# STM32.net
KiCad netlist of a schematic drawn in Altium Designer
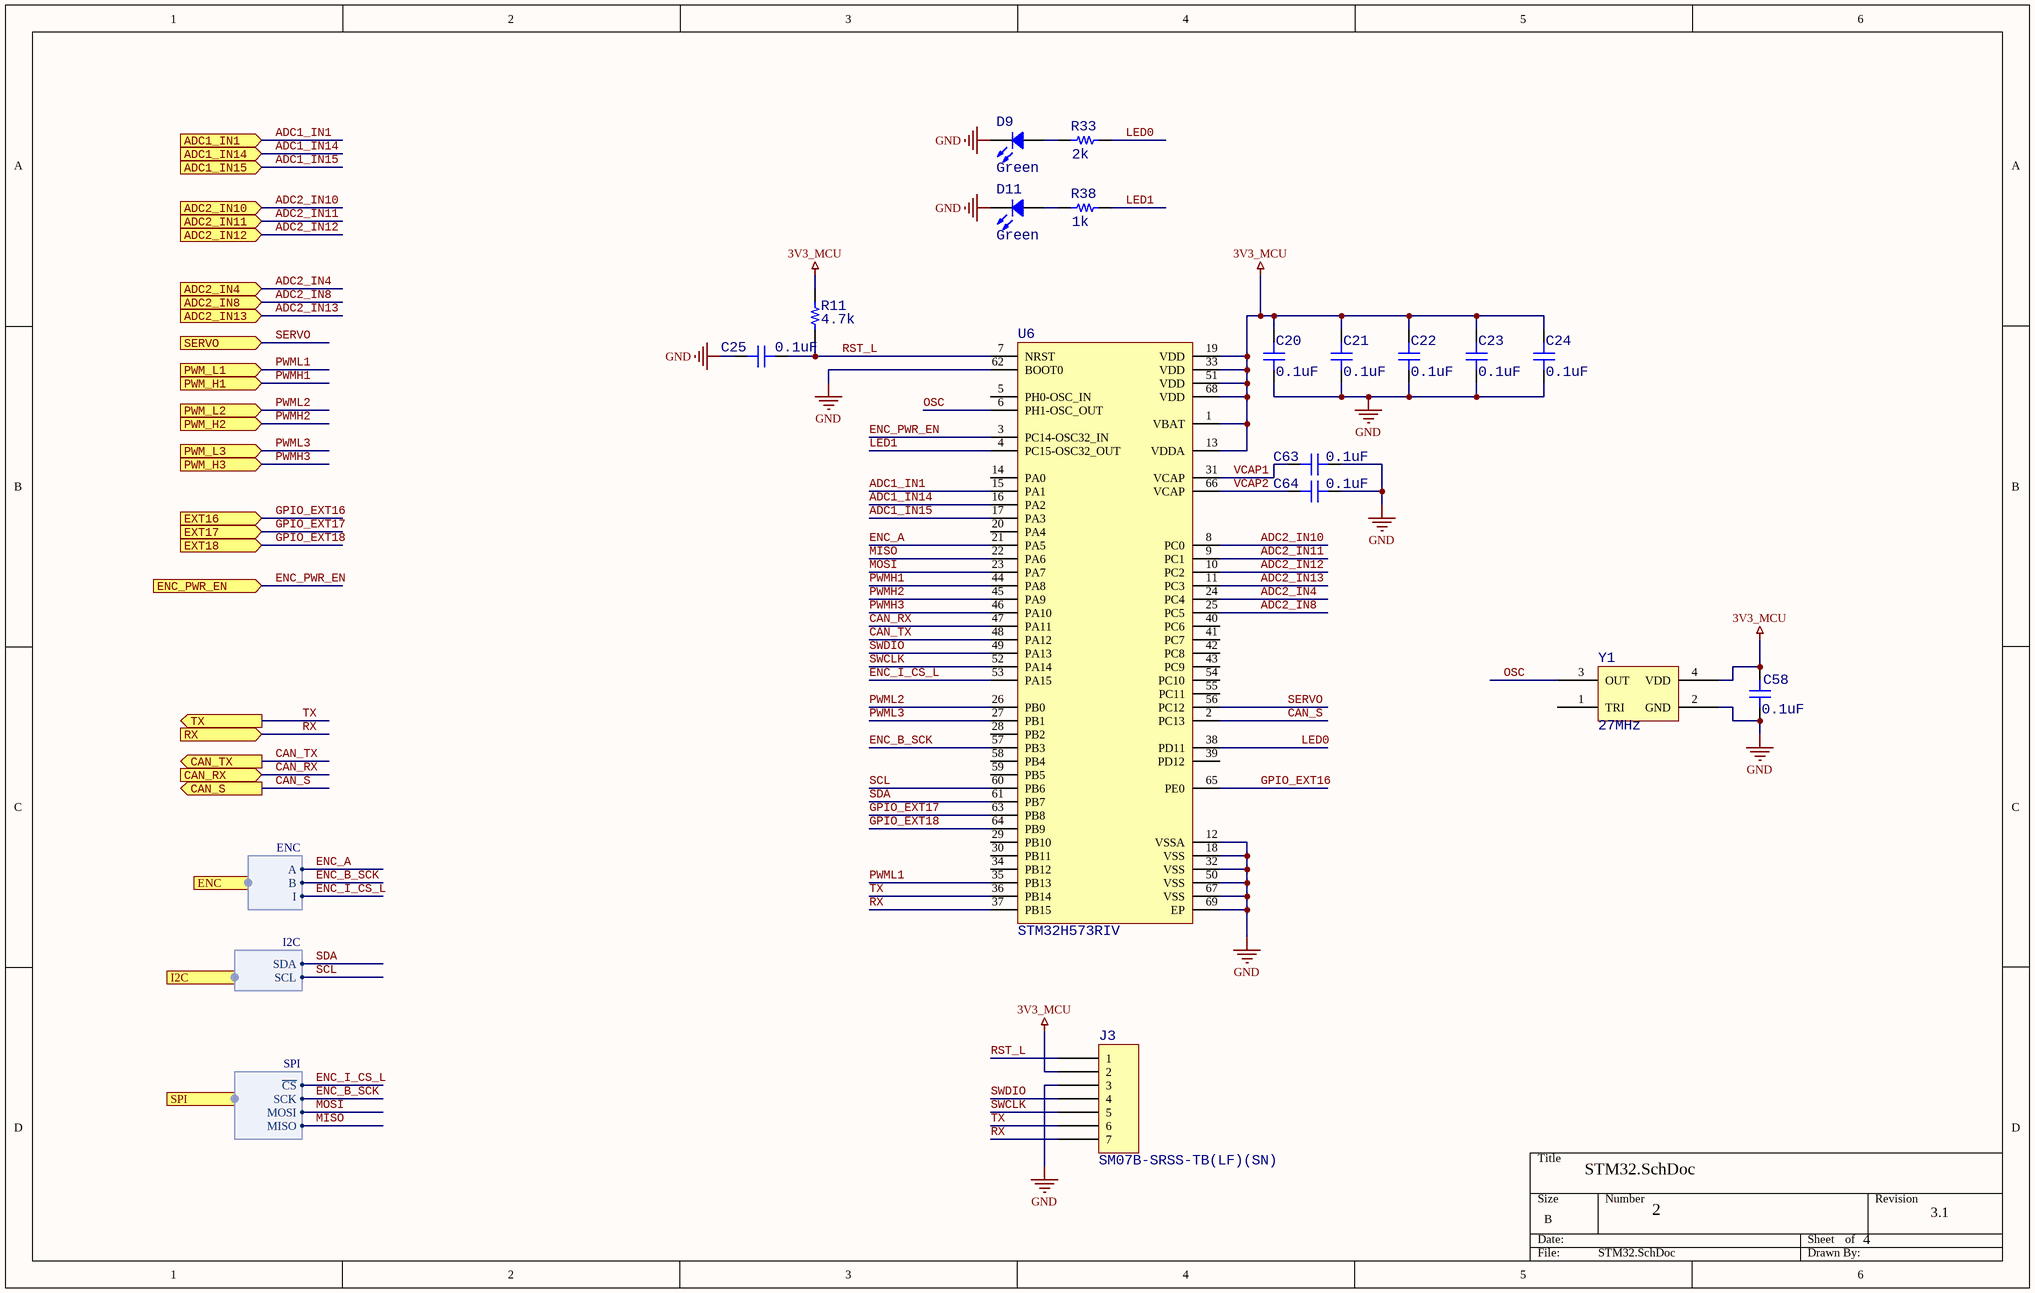
[diagram p0: STM32.SchDoc]

(export (version "E")
  (design (tool "Eeschema 10.0.6"))
  (components
    (comp (ref "C20")
      (value "0.1uF")
      (footprint "CAP_0402")
      (description "CAP CER 402")
      (libsource (lib "IC") (part "CAP_0402"))
    )
    (comp (ref "C21")
      (value "0.1uF")
      (footprint "CAP_0402")
      (description "CAP CER 402")
      (libsource (lib "IC") (part "CAP_0402"))
    )
    (comp (ref "C22")
      (value "0.1uF")
      (footprint "CAP_0402")
      (description "CAP CER 402")
      (libsource (lib "IC") (part "CAP_0402"))
    )
    (comp (ref "C23")
      (value "0.1uF")
      (footprint "CAP_0402")
      (description "CAP CER 402")
      (libsource (lib "IC") (part "CAP_0402"))
    )
    (comp (ref "C24")
      (value "0.1uF")
      (footprint "CAP_0402")
      (description "CAP CER 402")
      (libsource (lib "IC") (part "CAP_0402"))
    )
    (comp (ref "C25")
      (value "0.1uF")
      (footprint "CAP_0402")
      (description "CAP CER 402")
      (libsource (lib "IC") (part "CAP_0402"))
    )
    (comp (ref "C58")
      (value "0.1uF")
      (footprint "CAP_0402")
      (description "CAP CER 402")
      (libsource (lib "IC") (part "CAP_0402"))
    )
    (comp (ref "C63")
      (value "0.1uF")
      (footprint "CAP_0402")
      (description "CAP CER 402")
      (libsource (lib "IC") (part "CAP_0402"))
    )
    (comp (ref "C64")
      (value "0.1uF")
      (footprint "CAP_0402")
      (description "CAP CER 402")
      (libsource (lib "IC") (part "CAP_0402"))
    )
    (comp (ref "D9")
      (value "Green")
      (footprint "LED 0603_1608 GREEN")
      (description "LED GREEN CLEAR 2SMD")
      (fields (field (name "PART NUMBER") "XZCDGK53W-8VF") (field (name "MANUFACTURER") "SunLED"))
      (libsource (lib "Celestial Altium Library - altium_library") (part "LED"))
    )
    (comp (ref "D11")
      (value "Green")
      (footprint "LED 0603_1608 GREEN")
      (description "LED GREEN CLEAR 2SMD")
      (fields (field (name "PART NUMBER") "XZCDGK53W-8VF") (field (name "MANUFACTURER") "SunLED"))
      (libsource (lib "Celestial Altium Library - altium_library") (part "LED"))
    )
    (comp (ref "J3")
      (value "SM07B-SRSS-TB(LF)(SN)")
      (footprint "JST SM07B-SRSS-TB")
      (description "CONN HEADER SMD R/A 7POS 1MM")
      (fields (field (name "MANUFACTURER") "JST Sales America Inc."))
      (libsource (lib "Celestial Altium Library - altium_library") (part "7 Pin"))
    )
    (comp (ref "R11")
      (value "4.7k")
      (footprint "RES_0402")
      (description "RES 0402")
      (libsource (lib "IC") (part "RES_0402"))
    )
    (comp (ref "R33")
      (value "2k")
      (footprint "RES_0402")
      (description "RES 0402")
      (libsource (lib "IC") (part "RES_0402"))
    )
    (comp (ref "R38")
      (value "1k")
      (footprint "RES_0402")
      (description "RES 0402")
      (libsource (lib "IC") (part "RES_0402"))
    )
    (comp (ref "U6")
      (value "STM32H573RIV")
      (footprint "68-VFQFPN")
      (libsource (lib "IC") (part "STM32H573RIV"))
    )
    (comp (ref "Y1")
      (value "27MHz")
      (footprint "ABRACON ASD")
      (description "XTAL OSC XO 27.0000MHZ HCMOS SMD")
      (fields (field (name "PART NUMBER") "ASD3-27.000MHZ-EC-T") (field (name "MANUFACTURER") "Abracon LLC"))
      (libsource (lib "Celestial Altium Library - altium_library") (part "Abracon XO ASD"))
    )
  )
  (nets
    (net (code "4") (name "/ADC1_IN1") (class "Default")
      (node (ref "U6") (pin "15") (pinfunction "PA1_15") (pintype "passive"))
    )
    (net (code "5") (name "/ADC1_IN14") (class "Default")
      (node (ref "U6") (pin "16") (pinfunction "PA2_16") (pintype "passive"))
    )
    (net (code "6") (name "/ADC1_IN15") (class "Default")
      (node (ref "U6") (pin "17") (pinfunction "PA3_17") (pintype "passive"))
    )
    (net (code "7") (name "/ADC2_IN4") (class "Default")
      (node (ref "U6") (pin "24") (pinfunction "PC4_24") (pintype "passive"))
    )
    (net (code "8") (name "/ADC2_IN8") (class "Default")
      (node (ref "U6") (pin "25") (pinfunction "PC5_25") (pintype "passive"))
    )
    (net (code "9") (name "/ADC2_IN10") (class "Default")
      (node (ref "U6") (pin "8") (pinfunction "PC0_8") (pintype "passive"))
    )
    (net (code "10") (name "/ADC2_IN11") (class "Default")
      (node (ref "U6") (pin "9") (pinfunction "PC1_9") (pintype "passive"))
    )
    (net (code "11") (name "/ADC2_IN12") (class "Default")
      (node (ref "U6") (pin "10") (pinfunction "PC2_10") (pintype "passive"))
    )
    (net (code "12") (name "/ADC2_IN13") (class "Default")
      (node (ref "U6") (pin "11") (pinfunction "PC3_11") (pintype "passive"))
    )
    (net (code "13") (name "/CAN_RX") (class "Default")
      (node (ref "U6") (pin "47") (pinfunction "PA11_47") (pintype "passive"))
    )
    (net (code "14") (name "/CAN_S") (class "Default")
      (node (ref "U6") (pin "2") (pinfunction "PC13_2") (pintype "passive"))
    )
    (net (code "15") (name "/CAN_TX") (class "Default")
      (node (ref "U6") (pin "48") (pinfunction "PA12_48") (pintype "passive"))
    )
    (net (code "16") (name "/ENC_A") (class "Default")
      (node (ref "U6") (pin "21") (pinfunction "PA5_21") (pintype "passive"))
    )
    (net (code "17") (name "/ENC_B_SCK") (class "Default")
      (node (ref "U6") (pin "57") (pinfunction "PB3_57") (pintype "passive"))
    )
    (net (code "18") (name "/ENC_I_CS_L") (class "Default")
      (node (ref "U6") (pin "53") (pinfunction "PA15_53") (pintype "passive"))
    )
    (net (code "19") (name "/ENC_PWR_EN") (class "Default")
      (node (ref "U6") (pin "3") (pinfunction "PC14-OSC32_IN_3") (pintype "passive"))
    )
    (net (code "20") (name "/GPIO_EXT16") (class "Default")
      (node (ref "U6") (pin "65") (pinfunction "PE0_65") (pintype "passive"))
    )
    (net (code "21") (name "/GPIO_EXT17") (class "Default")
      (node (ref "U6") (pin "63") (pinfunction "PB8_63") (pintype "passive"))
    )
    (net (code "22") (name "/GPIO_EXT18") (class "Default")
      (node (ref "U6") (pin "64") (pinfunction "PB9_64") (pintype "passive"))
    )
    (net (code "23") (name "/LED0") (class "Default")
      (node (ref "R33") (pin "2") (pinfunction "2_2") (pintype "passive"))
      (node (ref "U6") (pin "38") (pinfunction "PD11_38") (pintype "passive"))
    )
    (net (code "24") (name "/LED1") (class "Default")
      (node (ref "R38") (pin "2") (pinfunction "2_2") (pintype "passive"))
      (node (ref "U6") (pin "4") (pinfunction "PC15-OSC32_OUT_4") (pintype "passive"))
    )
    (net (code "25") (name "/MISO") (class "Default")
      (node (ref "U6") (pin "22") (pinfunction "PA6_22") (pintype "passive"))
    )
    (net (code "26") (name "/MOSI") (class "Default")
      (node (ref "U6") (pin "23") (pinfunction "PA7_23") (pintype "passive"))
    )
    (net (code "27") (name "/OSC") (class "Default")
      (node (ref "U6") (pin "6") (pinfunction "PH1-OSC_OUT_6") (pintype "passive"))
      (node (ref "Y1") (pin "3") (pinfunction "OUT_3") (pintype "passive"))
    )
    (net (code "28") (name "/PWMH1") (class "Default")
      (node (ref "U6") (pin "44") (pinfunction "PA8_44") (pintype "passive"))
    )
    (net (code "29") (name "/PWMH2") (class "Default")
      (node (ref "U6") (pin "45") (pinfunction "PA9_45") (pintype "passive"))
    )
    (net (code "30") (name "/PWMH3") (class "Default")
      (node (ref "U6") (pin "46") (pinfunction "PA10_46") (pintype "passive"))
    )
    (net (code "31") (name "/PWML1") (class "Default")
      (node (ref "U6") (pin "35") (pinfunction "PB13_35") (pintype "passive"))
    )
    (net (code "32") (name "/PWML2") (class "Default")
      (node (ref "U6") (pin "26") (pinfunction "PB0_26") (pintype "passive"))
    )
    (net (code "33") (name "/PWML3") (class "Default")
      (node (ref "U6") (pin "27") (pinfunction "PB1_27") (pintype "passive"))
    )
    (net (code "34") (name "/RST_L") (class "Default")
      (node (ref "C25") (pin "1") (pinfunction "1_1") (pintype "passive"))
      (node (ref "J3") (pin "1") (pinfunction "1_1") (pintype "passive"))
      (node (ref "R11") (pin "1") (pinfunction "1_1") (pintype "passive"))
      (node (ref "U6") (pin "7") (pinfunction "NRST_7") (pintype "passive"))
    )
    (net (code "35") (name "/RX") (class "Default")
      (node (ref "J3") (pin "7") (pinfunction "7_7") (pintype "passive"))
      (node (ref "U6") (pin "37") (pinfunction "PB15_37") (pintype "passive"))
    )
    (net (code "36") (name "/SCL") (class "Default")
      (node (ref "U6") (pin "60") (pinfunction "PB6_60") (pintype "passive"))
    )
    (net (code "37") (name "/SDA") (class "Default")
      (node (ref "U6") (pin "61") (pinfunction "PB7_61") (pintype "passive"))
    )
    (net (code "38") (name "/SERVO") (class "Default")
      (node (ref "U6") (pin "56") (pinfunction "PC12_56") (pintype "passive"))
    )
    (net (code "39") (name "/SWCLK") (class "Default")
      (node (ref "J3") (pin "5") (pinfunction "5_5") (pintype "passive"))
      (node (ref "U6") (pin "52") (pinfunction "PA14_52") (pintype "passive"))
    )
    (net (code "40") (name "/SWDIO") (class "Default")
      (node (ref "J3") (pin "4") (pinfunction "4_4") (pintype "passive"))
      (node (ref "U6") (pin "49") (pinfunction "PA13_49") (pintype "passive"))
    )
    (net (code "41") (name "/TX") (class "Default")
      (node (ref "J3") (pin "6") (pinfunction "6_6") (pintype "passive"))
      (node (ref "U6") (pin "36") (pinfunction "PB14_36") (pintype "passive"))
    )
    (net (code "42") (name "/VCAP1") (class "Default")
      (node (ref "C63") (pin "2") (pinfunction "2_2") (pintype "passive"))
      (node (ref "U6") (pin "31") (pinfunction "VCAP_31") (pintype "passive"))
    )
    (net (code "43") (name "/VCAP2") (class "Default")
      (node (ref "C64") (pin "2") (pinfunction "2_2") (pintype "passive"))
      (node (ref "U6") (pin "66") (pinfunction "VCAP_66") (pintype "passive"))
    )
    (net (code "47") (name "3V3_MCU") (class "Default")
      (node (ref "C20") (pin "2") (pinfunction "2_2") (pintype "passive"))
      (node (ref "C21") (pin "2") (pinfunction "2_2") (pintype "passive"))
      (node (ref "C22") (pin "2") (pinfunction "2_2") (pintype "passive"))
      (node (ref "C23") (pin "2") (pinfunction "2_2") (pintype "passive"))
      (node (ref "C24") (pin "2") (pinfunction "2_2") (pintype "passive"))
      (node (ref "C58") (pin "2") (pinfunction "2_2") (pintype "passive"))
      (node (ref "J3") (pin "2") (pinfunction "2_2") (pintype "passive"))
      (node (ref "R11") (pin "2") (pinfunction "2_2") (pintype "passive"))
      (node (ref "U6") (pin "1") (pinfunction "VBAT_1") (pintype "passive"))
      (node (ref "U6") (pin "13") (pinfunction "VDDA_13") (pintype "passive"))
      (node (ref "U6") (pin "19") (pinfunction "VDD_19") (pintype "passive"))
      (node (ref "U6") (pin "33") (pinfunction "VDD_33") (pintype "passive"))
      (node (ref "U6") (pin "51") (pinfunction "VDD_51") (pintype "passive"))
      (node (ref "U6") (pin "68") (pinfunction "VDD_68") (pintype "passive"))
      (node (ref "Y1") (pin "4") (pinfunction "VDD_4") (pintype "passive"))
    )
    (net (code "48") (name "GND") (class "Default")
      (node (ref "C20") (pin "1") (pinfunction "1_1") (pintype "passive"))
      (node (ref "C21") (pin "1") (pinfunction "1_1") (pintype "passive"))
      (node (ref "C22") (pin "1") (pinfunction "1_1") (pintype "passive"))
      (node (ref "C23") (pin "1") (pinfunction "1_1") (pintype "passive"))
      (node (ref "C24") (pin "1") (pinfunction "1_1") (pintype "passive"))
      (node (ref "C25") (pin "2") (pinfunction "2_2") (pintype "passive"))
      (node (ref "C58") (pin "1") (pinfunction "1_1") (pintype "passive"))
      (node (ref "C63") (pin "1") (pinfunction "1_1") (pintype "passive"))
      (node (ref "C64") (pin "1") (pinfunction "1_1") (pintype "passive"))
      (node (ref "D11") (pin "2") (pinfunction "2_2") (pintype "passive"))
      (node (ref "D9") (pin "2") (pinfunction "2_2") (pintype "passive"))
      (node (ref "J3") (pin "3") (pinfunction "3_3") (pintype "passive"))
      (node (ref "U6") (pin "12") (pinfunction "VSSA_12") (pintype "passive"))
      (node (ref "U6") (pin "18") (pinfunction "VSS_18") (pintype "passive"))
      (node (ref "U6") (pin "32") (pinfunction "VSS_32") (pintype "passive"))
      (node (ref "U6") (pin "50") (pinfunction "VSS_50") (pintype "passive"))
      (node (ref "U6") (pin "62") (pinfunction "BOOT0_62") (pintype "passive"))
      (node (ref "U6") (pin "67") (pinfunction "VSS_67") (pintype "passive"))
      (node (ref "U6") (pin "69") (pinfunction "EP_69") (pintype "passive"))
      (node (ref "Y1") (pin "2") (pinfunction "GND_2") (pintype "passive"))
    )
    (net (code "49") (name "Net-(D9-Pad1)") (class "Default")
      (node (ref "D9") (pin "1") (pinfunction "1_1") (pintype "passive"))
      (node (ref "R33") (pin "1") (pinfunction "1_1") (pintype "passive"))
    )
    (net (code "50") (name "Net-(D11-Pad1)") (class "Default")
      (node (ref "D11") (pin "1") (pinfunction "1_1") (pintype "passive"))
      (node (ref "R38") (pin "1") (pinfunction "1_1") (pintype "passive"))
    )
    (net (code "51") (name "unconnected-(U6-PA0-Pad14)") (class "Default")
      (node (ref "U6") (pin "14") (pinfunction "PA0_14") (pintype "passive"))
    )
    (net (code "52") (name "unconnected-(U6-PA4-Pad20)") (class "Default")
      (node (ref "U6") (pin "20") (pinfunction "PA4_20") (pintype "passive"))
    )
    (net (code "53") (name "unconnected-(U6-PB2-Pad28)") (class "Default")
      (node (ref "U6") (pin "28") (pinfunction "PB2_28") (pintype "passive"))
    )
    (net (code "54") (name "unconnected-(U6-PB4-Pad58)") (class "Default")
      (node (ref "U6") (pin "58") (pinfunction "PB4_58") (pintype "passive"))
    )
    (net (code "55") (name "unconnected-(U6-PB5-Pad59)") (class "Default")
      (node (ref "U6") (pin "59") (pinfunction "PB5_59") (pintype "passive"))
    )
    (net (code "56") (name "unconnected-(U6-PB10-Pad29)") (class "Default")
      (node (ref "U6") (pin "29") (pinfunction "PB10_29") (pintype "passive"))
    )
    (net (code "57") (name "unconnected-(U6-PB11-Pad30)") (class "Default")
      (node (ref "U6") (pin "30") (pinfunction "PB11_30") (pintype "passive"))
    )
    (net (code "58") (name "unconnected-(U6-PB12-Pad34)") (class "Default")
      (node (ref "U6") (pin "34") (pinfunction "PB12_34") (pintype "passive"))
    )
    (net (code "59") (name "unconnected-(U6-PC6-Pad40)") (class "Default")
      (node (ref "U6") (pin "40") (pinfunction "PC6_40") (pintype "passive"))
    )
    (net (code "60") (name "unconnected-(U6-PC7-Pad41)") (class "Default")
      (node (ref "U6") (pin "41") (pinfunction "PC7_41") (pintype "passive"))
    )
    (net (code "61") (name "unconnected-(U6-PC8-Pad42)") (class "Default")
      (node (ref "U6") (pin "42") (pinfunction "PC8_42") (pintype "passive"))
    )
    (net (code "62") (name "unconnected-(U6-PC9-Pad43)") (class "Default")
      (node (ref "U6") (pin "43") (pinfunction "PC9_43") (pintype "passive"))
    )
    (net (code "63") (name "unconnected-(U6-PC10-Pad54)") (class "Default")
      (node (ref "U6") (pin "54") (pinfunction "PC10_54") (pintype "passive"))
    )
    (net (code "64") (name "unconnected-(U6-PC11-Pad55)") (class "Default")
      (node (ref "U6") (pin "55") (pinfunction "PC11_55") (pintype "passive"))
    )
    (net (code "65") (name "unconnected-(U6-PD12-Pad39)") (class "Default")
      (node (ref "U6") (pin "39") (pinfunction "PD12_39") (pintype "passive"))
    )
    (net (code "66") (name "unconnected-(U6-PH0-OSC_IN-Pad5)") (class "Default")
      (node (ref "U6") (pin "5") (pinfunction "PH0-OSC_IN_5") (pintype "passive"))
    )
    (net (code "67") (name "unconnected-(Y1-TRI-Pad1)") (class "Default")
      (node (ref "Y1") (pin "1") (pinfunction "TRI_1") (pintype "passive"))
    )
  )
)
